# input_board.net
KiCad netlist of a schematic drawn in EAGLE
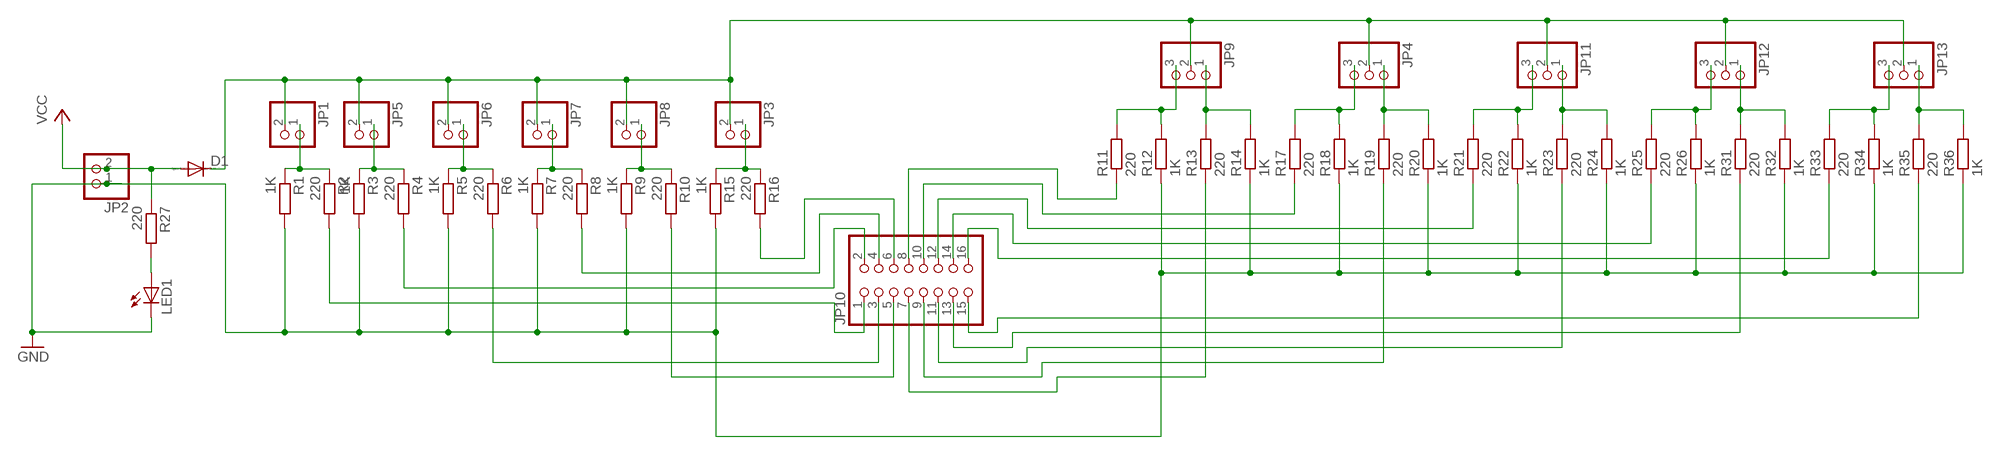
[diagram p0: schematic, sheet 1]

(export (version "E")
  (design (tool "Eeschema 10.0.6"))
  (components
    (comp (ref "D1")
      (value "DIODE-C1702-05")
      (footprint "eagle-import:C1702-05")
      (libsource (lib "eagle-import") (part "DIODE-C1702-05"))
    )
    (comp (ref "JP1")
      (value "PINHD-1X2")
      (footprint "eagle-import:1X02")
      (libsource (lib "eagle-import") (part "PINHD-1X2"))
    )
    (comp (ref "JP2")
      (value "PINHD-1X2")
      (footprint "eagle-import:1X02")
      (libsource (lib "eagle-import") (part "PINHD-1X2"))
    )
    (comp (ref "JP3")
      (value "PINHD-1X2")
      (footprint "eagle-import:1X02")
      (libsource (lib "eagle-import") (part "PINHD-1X2"))
    )
    (comp (ref "JP4")
      (value "PINHD-1X3")
      (footprint "eagle-import:1X03")
      (libsource (lib "eagle-import") (part "PINHD-1X3"))
    )
    (comp (ref "JP5")
      (value "PINHD-1X2")
      (footprint "eagle-import:1X02")
      (libsource (lib "eagle-import") (part "PINHD-1X2"))
    )
    (comp (ref "JP6")
      (value "PINHD-1X2")
      (footprint "eagle-import:1X02")
      (libsource (lib "eagle-import") (part "PINHD-1X2"))
    )
    (comp (ref "JP7")
      (value "PINHD-1X2")
      (footprint "eagle-import:1X02")
      (libsource (lib "eagle-import") (part "PINHD-1X2"))
    )
    (comp (ref "JP8")
      (value "PINHD-1X2")
      (footprint "eagle-import:1X02")
      (libsource (lib "eagle-import") (part "PINHD-1X2"))
    )
    (comp (ref "JP9")
      (value "PINHD-1X3")
      (footprint "eagle-import:1X03")
      (libsource (lib "eagle-import") (part "PINHD-1X3"))
    )
    (comp (ref "JP10")
      (value "PINHD-2X8")
      (footprint "eagle-import:2X08")
      (libsource (lib "eagle-import") (part "PINHD-2X8"))
    )
    (comp (ref "JP11")
      (value "PINHD-1X3")
      (footprint "eagle-import:1X03")
      (libsource (lib "eagle-import") (part "PINHD-1X3"))
    )
    (comp (ref "JP12")
      (value "PINHD-1X3")
      (footprint "eagle-import:1X03")
      (libsource (lib "eagle-import") (part "PINHD-1X3"))
    )
    (comp (ref "JP13")
      (value "PINHD-1X3")
      (footprint "eagle-import:1X03")
      (libsource (lib "eagle-import") (part "PINHD-1X3"))
    )
    (comp (ref "LED1")
      (value "LED3MM")
      (footprint "eagle-import:LED3MM")
      (libsource (lib "eagle-import") (part "LED3MM"))
    )
    (comp (ref "R1")
      (value "1K")
      (footprint "eagle-import:0204V")
      (libsource (lib "eagle-import") (part "R-EU_0204/2V"))
    )
    (comp (ref "R2")
      (value "220")
      (footprint "eagle-import:0204V")
      (libsource (lib "eagle-import") (part "R-EU_0204/2V"))
    )
    (comp (ref "R3")
      (value "1K")
      (footprint "eagle-import:0204V")
      (libsource (lib "eagle-import") (part "R-EU_0204/2V"))
    )
    (comp (ref "R4")
      (value "220")
      (footprint "eagle-import:0204V")
      (libsource (lib "eagle-import") (part "R-EU_0204/2V"))
    )
    (comp (ref "R5")
      (value "1K")
      (footprint "eagle-import:0204V")
      (libsource (lib "eagle-import") (part "R-EU_0204/2V"))
    )
    (comp (ref "R6")
      (value "220")
      (footprint "eagle-import:0204V")
      (libsource (lib "eagle-import") (part "R-EU_0204/2V"))
    )
    (comp (ref "R7")
      (value "1K")
      (footprint "eagle-import:0204V")
      (libsource (lib "eagle-import") (part "R-EU_0204/2V"))
    )
    (comp (ref "R8")
      (value "220")
      (footprint "eagle-import:0204V")
      (libsource (lib "eagle-import") (part "R-EU_0204/2V"))
    )
    (comp (ref "R9")
      (value "1K")
      (footprint "eagle-import:0204V")
      (libsource (lib "eagle-import") (part "R-EU_0204/2V"))
    )
    (comp (ref "R10")
      (value "220")
      (footprint "eagle-import:0204V")
      (libsource (lib "eagle-import") (part "R-EU_0204/2V"))
    )
    (comp (ref "R11")
      (value "220")
      (footprint "eagle-import:0204V")
      (libsource (lib "eagle-import") (part "R-EU_0204/2V"))
    )
    (comp (ref "R12")
      (value "1K")
      (footprint "eagle-import:0204V")
      (libsource (lib "eagle-import") (part "R-EU_0204/2V"))
    )
    (comp (ref "R13")
      (value "220")
      (footprint "eagle-import:0204V")
      (libsource (lib "eagle-import") (part "R-EU_0204/2V"))
    )
    (comp (ref "R14")
      (value "1K")
      (footprint "eagle-import:0204V")
      (libsource (lib "eagle-import") (part "R-EU_0204/2V"))
    )
    (comp (ref "R15")
      (value "1K")
      (footprint "eagle-import:0204V")
      (libsource (lib "eagle-import") (part "R-EU_0204/2V"))
    )
    (comp (ref "R16")
      (value "220")
      (footprint "eagle-import:0204V")
      (libsource (lib "eagle-import") (part "R-EU_0204/2V"))
    )
    (comp (ref "R17")
      (value "220")
      (footprint "eagle-import:0204V")
      (libsource (lib "eagle-import") (part "R-EU_0204/2V"))
    )
    (comp (ref "R18")
      (value "1K")
      (footprint "eagle-import:0204V")
      (libsource (lib "eagle-import") (part "R-EU_0204/2V"))
    )
    (comp (ref "R19")
      (value "220")
      (footprint "eagle-import:0204V")
      (libsource (lib "eagle-import") (part "R-EU_0204/2V"))
    )
    (comp (ref "R20")
      (value "1K")
      (footprint "eagle-import:0204V")
      (libsource (lib "eagle-import") (part "R-EU_0204/2V"))
    )
    (comp (ref "R21")
      (value "220")
      (footprint "eagle-import:0204V")
      (libsource (lib "eagle-import") (part "R-EU_0204/2V"))
    )
    (comp (ref "R22")
      (value "1K")
      (footprint "eagle-import:0204V")
      (libsource (lib "eagle-import") (part "R-EU_0204/2V"))
    )
    (comp (ref "R23")
      (value "220")
      (footprint "eagle-import:0204V")
      (libsource (lib "eagle-import") (part "R-EU_0204/2V"))
    )
    (comp (ref "R24")
      (value "1K")
      (footprint "eagle-import:0204V")
      (libsource (lib "eagle-import") (part "R-EU_0204/2V"))
    )
    (comp (ref "R25")
      (value "220")
      (footprint "eagle-import:0204V")
      (libsource (lib "eagle-import") (part "R-EU_0204/2V"))
    )
    (comp (ref "R26")
      (value "1K")
      (footprint "eagle-import:0204V")
      (libsource (lib "eagle-import") (part "R-EU_0204/2V"))
    )
    (comp (ref "R27")
      (value "220")
      (footprint "eagle-import:0204V")
      (libsource (lib "eagle-import") (part "R-EU_0204/2V"))
    )
    (comp (ref "R31")
      (value "220")
      (footprint "eagle-import:0204V")
      (libsource (lib "eagle-import") (part "R-EU_0204/2V"))
    )
    (comp (ref "R32")
      (value "1K")
      (footprint "eagle-import:0204V")
      (libsource (lib "eagle-import") (part "R-EU_0204/2V"))
    )
    (comp (ref "R33")
      (value "220")
      (footprint "eagle-import:0204V")
      (libsource (lib "eagle-import") (part "R-EU_0204/2V"))
    )
    (comp (ref "R34")
      (value "1K")
      (footprint "eagle-import:0204V")
      (libsource (lib "eagle-import") (part "R-EU_0204/2V"))
    )
    (comp (ref "R35")
      (value "220")
      (footprint "eagle-import:0204V")
      (libsource (lib "eagle-import") (part "R-EU_0204/2V"))
    )
    (comp (ref "R36")
      (value "1K")
      (footprint "eagle-import:0204V")
      (libsource (lib "eagle-import") (part "R-EU_0204/2V"))
    )
  )
  (nets
    (net (code "1") (name "GND") (class "Default")
      (node (ref "JP2") (pin "1") (pinfunction "1_1") (pintype "passive"))
      (node (ref "LED1") (pin "K") (pinfunction "C_K") (pintype "passive"))
      (node (ref "R1") (pin "2") (pinfunction "2_2") (pintype "passive"))
      (node (ref "R12") (pin "1") (pinfunction "1_1") (pintype "passive"))
      (node (ref "R14") (pin "1") (pinfunction "1_1") (pintype "passive"))
      (node (ref "R15") (pin "2") (pinfunction "2_2") (pintype "passive"))
      (node (ref "R18") (pin "1") (pinfunction "1_1") (pintype "passive"))
      (node (ref "R20") (pin "1") (pinfunction "1_1") (pintype "passive"))
      (node (ref "R22") (pin "1") (pinfunction "1_1") (pintype "passive"))
      (node (ref "R24") (pin "1") (pinfunction "1_1") (pintype "passive"))
      (node (ref "R26") (pin "1") (pinfunction "1_1") (pintype "passive"))
      (node (ref "R3") (pin "2") (pinfunction "2_2") (pintype "passive"))
      (node (ref "R32") (pin "1") (pinfunction "1_1") (pintype "passive"))
      (node (ref "R34") (pin "1") (pinfunction "1_1") (pintype "passive"))
      (node (ref "R36") (pin "1") (pinfunction "1_1") (pintype "passive"))
      (node (ref "R5") (pin "2") (pinfunction "2_2") (pintype "passive"))
      (node (ref "R7") (pin "2") (pinfunction "2_2") (pintype "passive"))
      (node (ref "R9") (pin "2") (pinfunction "2_2") (pintype "passive"))
    )
    (net (code "2") (name "Net-(D1-PadC)") (class "Default")
      (node (ref "D1") (pin "C") (pinfunction "C_C") (pintype "passive"))
      (node (ref "JP1") (pin "2") (pinfunction "2_2") (pintype "passive"))
      (node (ref "JP11") (pin "2") (pinfunction "2_2") (pintype "passive"))
      (node (ref "JP12") (pin "2") (pinfunction "2_2") (pintype "passive"))
      (node (ref "JP13") (pin "2") (pinfunction "2_2") (pintype "passive"))
      (node (ref "JP3") (pin "2") (pinfunction "2_2") (pintype "passive"))
      (node (ref "JP4") (pin "2") (pinfunction "2_2") (pintype "passive"))
      (node (ref "JP5") (pin "2") (pinfunction "2_2") (pintype "passive"))
      (node (ref "JP6") (pin "2") (pinfunction "2_2") (pintype "passive"))
      (node (ref "JP7") (pin "2") (pinfunction "2_2") (pintype "passive"))
      (node (ref "JP8") (pin "2") (pinfunction "2_2") (pintype "passive"))
      (node (ref "JP9") (pin "2") (pinfunction "2_2") (pintype "passive"))
    )
    (net (code "3") (name "Net-(JP1-Pad1)") (class "Default")
      (node (ref "JP1") (pin "1") (pinfunction "1_1") (pintype "passive"))
      (node (ref "R1") (pin "1") (pinfunction "1_1") (pintype "passive"))
      (node (ref "R2") (pin "1") (pinfunction "1_1") (pintype "passive"))
    )
    (net (code "4") (name "Net-(JP3-Pad1)") (class "Default")
      (node (ref "JP3") (pin "1") (pinfunction "1_1") (pintype "passive"))
      (node (ref "R15") (pin "1") (pinfunction "1_1") (pintype "passive"))
      (node (ref "R16") (pin "1") (pinfunction "1_1") (pintype "passive"))
    )
    (net (code "5") (name "Net-(JP4-Pad1)") (class "Default")
      (node (ref "JP4") (pin "1") (pinfunction "1_1") (pintype "passive"))
      (node (ref "R19") (pin "2") (pinfunction "2_2") (pintype "passive"))
      (node (ref "R20") (pin "2") (pinfunction "2_2") (pintype "passive"))
    )
    (net (code "6") (name "Net-(JP4-Pad3)") (class "Default")
      (node (ref "JP4") (pin "3") (pinfunction "3_3") (pintype "passive"))
      (node (ref "R17") (pin "2") (pinfunction "2_2") (pintype "passive"))
      (node (ref "R18") (pin "2") (pinfunction "2_2") (pintype "passive"))
    )
    (net (code "7") (name "Net-(JP5-Pad1)") (class "Default")
      (node (ref "JP5") (pin "1") (pinfunction "1_1") (pintype "passive"))
      (node (ref "R3") (pin "1") (pinfunction "1_1") (pintype "passive"))
      (node (ref "R4") (pin "1") (pinfunction "1_1") (pintype "passive"))
    )
    (net (code "8") (name "Net-(JP6-Pad1)") (class "Default")
      (node (ref "JP6") (pin "1") (pinfunction "1_1") (pintype "passive"))
      (node (ref "R5") (pin "1") (pinfunction "1_1") (pintype "passive"))
      (node (ref "R6") (pin "1") (pinfunction "1_1") (pintype "passive"))
    )
    (net (code "9") (name "Net-(JP7-Pad1)") (class "Default")
      (node (ref "JP7") (pin "1") (pinfunction "1_1") (pintype "passive"))
      (node (ref "R7") (pin "1") (pinfunction "1_1") (pintype "passive"))
      (node (ref "R8") (pin "1") (pinfunction "1_1") (pintype "passive"))
    )
    (net (code "10") (name "Net-(JP8-Pad1)") (class "Default")
      (node (ref "JP8") (pin "1") (pinfunction "1_1") (pintype "passive"))
      (node (ref "R10") (pin "1") (pinfunction "1_1") (pintype "passive"))
      (node (ref "R9") (pin "1") (pinfunction "1_1") (pintype "passive"))
    )
    (net (code "11") (name "Net-(JP9-Pad1)") (class "Default")
      (node (ref "JP9") (pin "1") (pinfunction "1_1") (pintype "passive"))
      (node (ref "R13") (pin "2") (pinfunction "2_2") (pintype "passive"))
      (node (ref "R14") (pin "2") (pinfunction "2_2") (pintype "passive"))
    )
    (net (code "12") (name "Net-(JP9-Pad3)") (class "Default")
      (node (ref "JP9") (pin "3") (pinfunction "3_3") (pintype "passive"))
      (node (ref "R11") (pin "2") (pinfunction "2_2") (pintype "passive"))
      (node (ref "R12") (pin "2") (pinfunction "2_2") (pintype "passive"))
    )
    (net (code "13") (name "Net-(JP10-Pad1)") (class "Default")
      (node (ref "JP10") (pin "1") (pinfunction "1_1") (pintype "passive"))
      (node (ref "R2") (pin "2") (pinfunction "2_2") (pintype "passive"))
    )
    (net (code "14") (name "Net-(JP10-Pad2)") (class "Default")
      (node (ref "JP10") (pin "2") (pinfunction "2_2") (pintype "passive"))
      (node (ref "R4") (pin "2") (pinfunction "2_2") (pintype "passive"))
    )
    (net (code "15") (name "Net-(JP10-Pad3)") (class "Default")
      (node (ref "JP10") (pin "3") (pinfunction "3_3") (pintype "passive"))
      (node (ref "R6") (pin "2") (pinfunction "2_2") (pintype "passive"))
    )
    (net (code "16") (name "Net-(JP10-Pad4)") (class "Default")
      (node (ref "JP10") (pin "4") (pinfunction "4_4") (pintype "passive"))
      (node (ref "R8") (pin "2") (pinfunction "2_2") (pintype "passive"))
    )
    (net (code "17") (name "Net-(JP10-Pad5)") (class "Default")
      (node (ref "JP10") (pin "5") (pinfunction "5_5") (pintype "passive"))
      (node (ref "R10") (pin "2") (pinfunction "2_2") (pintype "passive"))
    )
    (net (code "18") (name "Net-(JP10-Pad6)") (class "Default")
      (node (ref "JP10") (pin "6") (pinfunction "6_6") (pintype "passive"))
      (node (ref "R16") (pin "2") (pinfunction "2_2") (pintype "passive"))
    )
    (net (code "19") (name "Net-(JP10-Pad7)") (class "Default")
      (node (ref "JP10") (pin "7") (pinfunction "7_7") (pintype "passive"))
      (node (ref "R13") (pin "1") (pinfunction "1_1") (pintype "passive"))
    )
    (net (code "20") (name "Net-(JP10-Pad8)") (class "Default")
      (node (ref "JP10") (pin "8") (pinfunction "8_8") (pintype "passive"))
      (node (ref "R11") (pin "1") (pinfunction "1_1") (pintype "passive"))
    )
    (net (code "21") (name "Net-(JP10-Pad9)") (class "Default")
      (node (ref "JP10") (pin "9") (pinfunction "9_9") (pintype "passive"))
      (node (ref "R19") (pin "1") (pinfunction "1_1") (pintype "passive"))
    )
    (net (code "22") (name "Net-(JP10-Pad10)") (class "Default")
      (node (ref "JP10") (pin "10") (pinfunction "10_10") (pintype "passive"))
      (node (ref "R17") (pin "1") (pinfunction "1_1") (pintype "passive"))
    )
    (net (code "23") (name "Net-(JP10-Pad11)") (class "Default")
      (node (ref "JP10") (pin "11") (pinfunction "11_11") (pintype "passive"))
      (node (ref "R23") (pin "1") (pinfunction "1_1") (pintype "passive"))
    )
    (net (code "24") (name "Net-(JP10-Pad12)") (class "Default")
      (node (ref "JP10") (pin "12") (pinfunction "12_12") (pintype "passive"))
      (node (ref "R21") (pin "1") (pinfunction "1_1") (pintype "passive"))
    )
    (net (code "25") (name "Net-(JP10-Pad13)") (class "Default")
      (node (ref "JP10") (pin "13") (pinfunction "13_13") (pintype "passive"))
      (node (ref "R31") (pin "1") (pinfunction "1_1") (pintype "passive"))
    )
    (net (code "26") (name "Net-(JP10-Pad14)") (class "Default")
      (node (ref "JP10") (pin "14") (pinfunction "14_14") (pintype "passive"))
      (node (ref "R25") (pin "1") (pinfunction "1_1") (pintype "passive"))
    )
    (net (code "27") (name "Net-(JP10-Pad15)") (class "Default")
      (node (ref "JP10") (pin "15") (pinfunction "15_15") (pintype "passive"))
      (node (ref "R35") (pin "1") (pinfunction "1_1") (pintype "passive"))
    )
    (net (code "28") (name "Net-(JP10-Pad16)") (class "Default")
      (node (ref "JP10") (pin "16") (pinfunction "16_16") (pintype "passive"))
      (node (ref "R33") (pin "1") (pinfunction "1_1") (pintype "passive"))
    )
    (net (code "29") (name "Net-(JP11-Pad1)") (class "Default")
      (node (ref "JP11") (pin "1") (pinfunction "1_1") (pintype "passive"))
      (node (ref "R23") (pin "2") (pinfunction "2_2") (pintype "passive"))
      (node (ref "R24") (pin "2") (pinfunction "2_2") (pintype "passive"))
    )
    (net (code "30") (name "Net-(JP11-Pad3)") (class "Default")
      (node (ref "JP11") (pin "3") (pinfunction "3_3") (pintype "passive"))
      (node (ref "R21") (pin "2") (pinfunction "2_2") (pintype "passive"))
      (node (ref "R22") (pin "2") (pinfunction "2_2") (pintype "passive"))
    )
    (net (code "31") (name "Net-(JP12-Pad1)") (class "Default")
      (node (ref "JP12") (pin "1") (pinfunction "1_1") (pintype "passive"))
      (node (ref "R31") (pin "2") (pinfunction "2_2") (pintype "passive"))
      (node (ref "R32") (pin "2") (pinfunction "2_2") (pintype "passive"))
    )
    (net (code "32") (name "Net-(JP12-Pad3)") (class "Default")
      (node (ref "JP12") (pin "3") (pinfunction "3_3") (pintype "passive"))
      (node (ref "R25") (pin "2") (pinfunction "2_2") (pintype "passive"))
      (node (ref "R26") (pin "2") (pinfunction "2_2") (pintype "passive"))
    )
    (net (code "33") (name "Net-(JP13-Pad1)") (class "Default")
      (node (ref "JP13") (pin "1") (pinfunction "1_1") (pintype "passive"))
      (node (ref "R35") (pin "2") (pinfunction "2_2") (pintype "passive"))
      (node (ref "R36") (pin "2") (pinfunction "2_2") (pintype "passive"))
    )
    (net (code "34") (name "Net-(JP13-Pad3)") (class "Default")
      (node (ref "JP13") (pin "3") (pinfunction "3_3") (pintype "passive"))
      (node (ref "R33") (pin "2") (pinfunction "2_2") (pintype "passive"))
      (node (ref "R34") (pin "2") (pinfunction "2_2") (pintype "passive"))
    )
    (net (code "35") (name "Net-(LED1-PadA)") (class "Default")
      (node (ref "LED1") (pin "A") (pinfunction "A_A") (pintype "passive"))
      (node (ref "R27") (pin "2") (pinfunction "2_2") (pintype "passive"))
    )
    (net (code "36") (name "VCC") (class "Default")
      (node (ref "D1") (pin "A") (pinfunction "A_A") (pintype "passive"))
      (node (ref "JP2") (pin "2") (pinfunction "2_2") (pintype "passive"))
      (node (ref "R27") (pin "1") (pinfunction "1_1") (pintype "passive"))
    )
  )
)
